# tulip_breakout.net
KiCad netlist of a schematic drawn in EAGLE
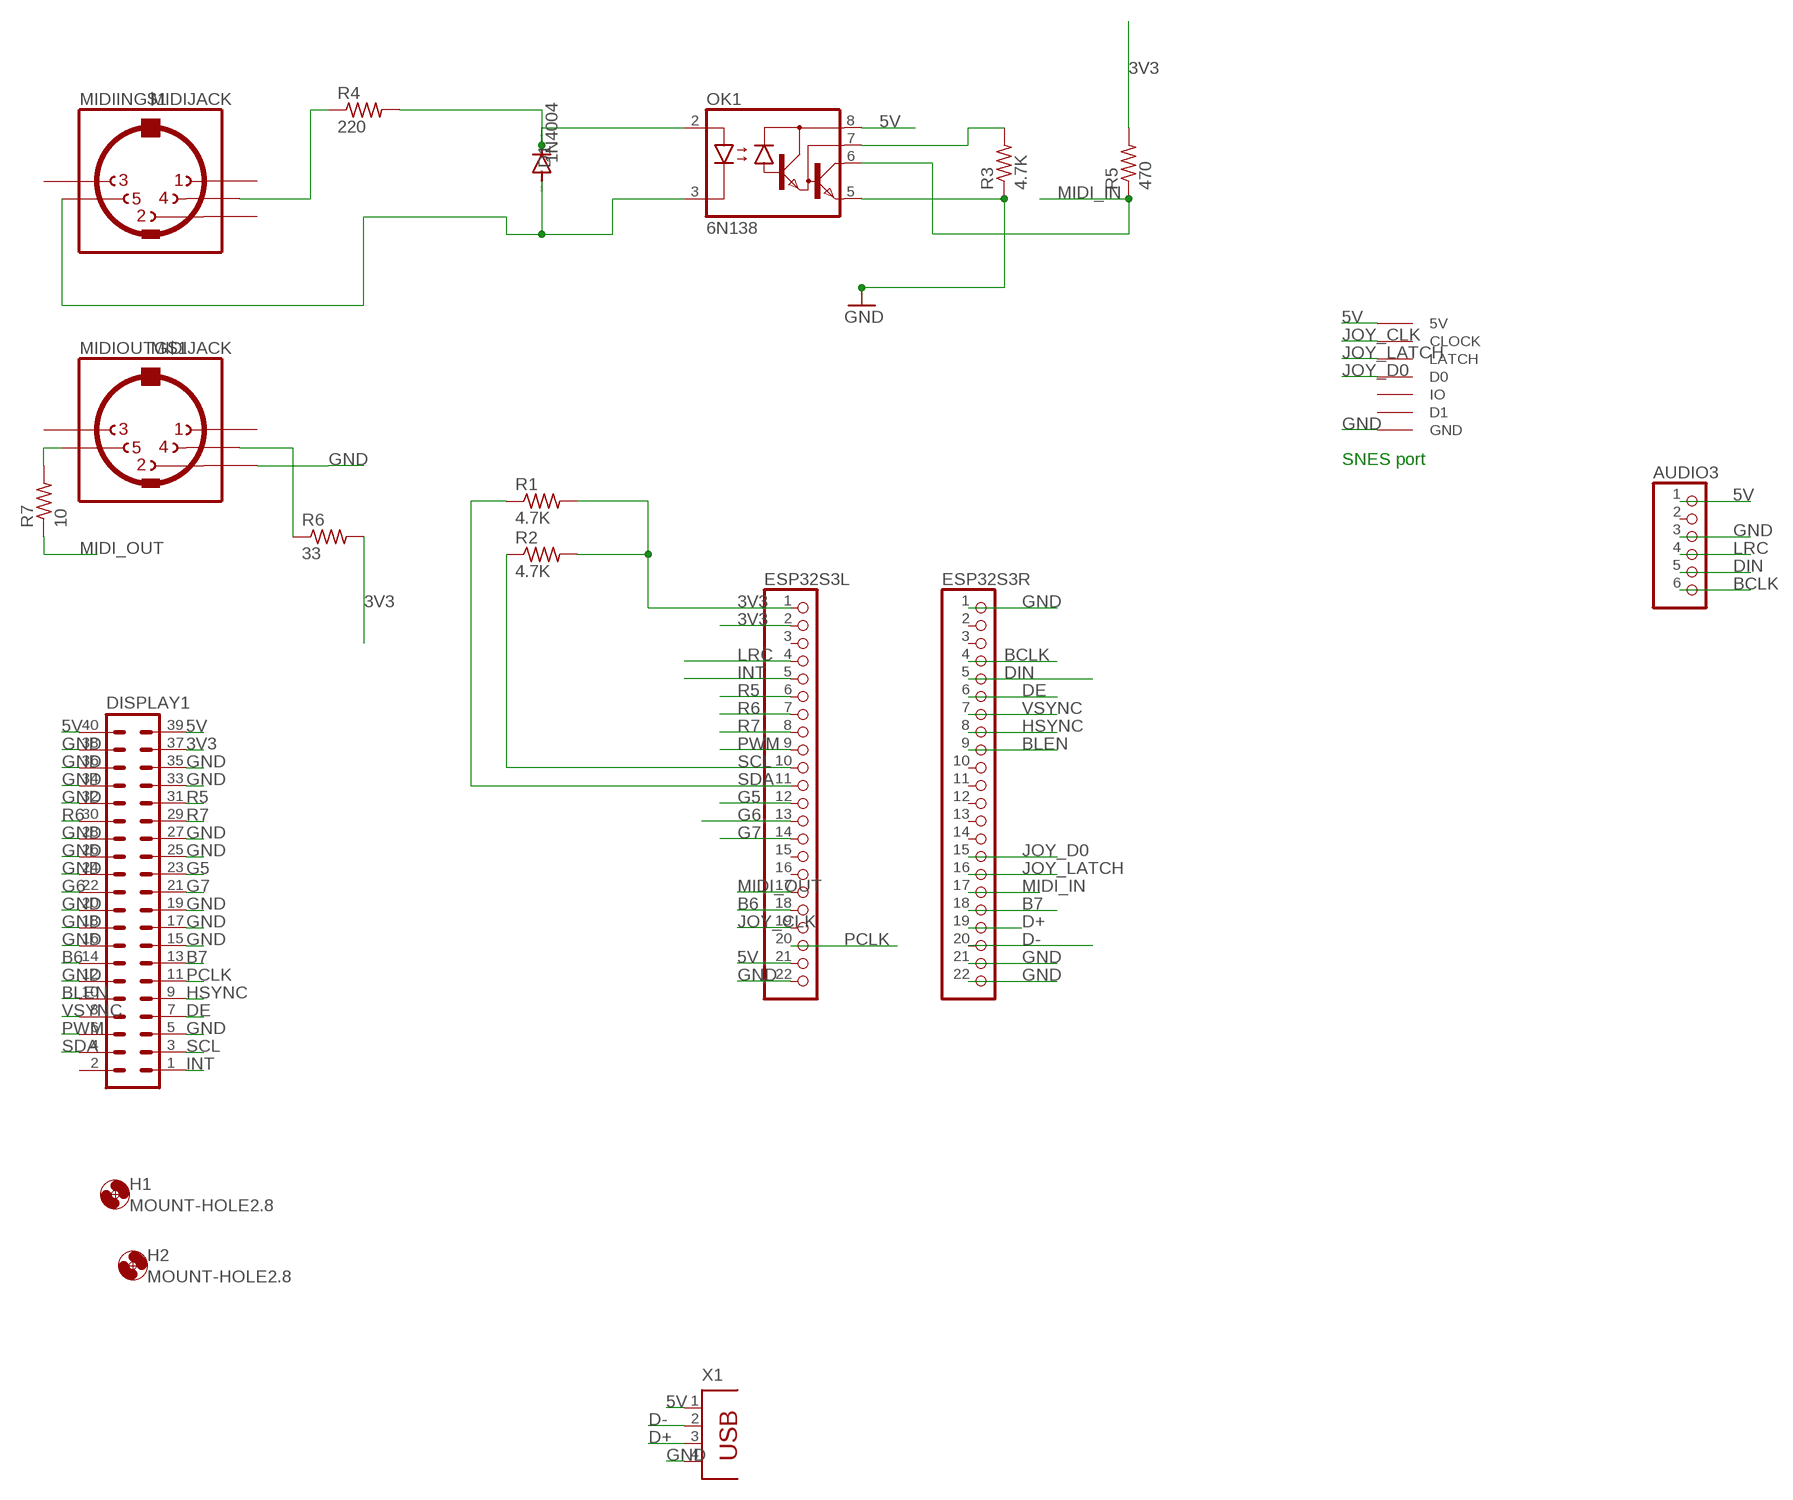
[diagram p0: schematic, sheet 1]

(export (version "E")
  (design (tool "Eeschema 10.0.6"))
  (components
    (comp (ref "AUDIO3")
      (value "PINHD-1X6")
      (footprint "eagle-import:1X06")
      (libsource (lib "eagle-import") (part "PINHD-1X6"))
    )
    (comp (ref "D1")
      (value "1N4004")
      (footprint "eagle-import:DO41-10")
      (libsource (lib "eagle-import") (part "1N4004"))
    )
    (comp (ref "DISPLAY1")
      (value "MA20-2")
      (footprint "eagle-import:MA20-2")
      (libsource (lib "eagle-import") (part "MA20-2"))
    )
    (comp (ref "ESP32S3L")
      (value "PINHD-1X22")
      (footprint "eagle-import:1X22")
      (libsource (lib "eagle-import") (part "PINHD-1X22"))
    )
    (comp (ref "ESP32S3R")
      (value "PINHD-1X22")
      (footprint "eagle-import:1X22")
      (libsource (lib "eagle-import") (part "PINHD-1X22"))
    )
    (comp (ref "H1")
      (value "MOUNT-HOLE2.8")
      (footprint "eagle-import:2,8")
      (libsource (lib "eagle-import") (part "MOUNT-HOLE2.8"))
    )
    (comp (ref "H2")
      (value "MOUNT-HOLE2.8")
      (footprint "eagle-import:2,8")
      (libsource (lib "eagle-import") (part "MOUNT-HOLE2.8"))
    )
    (comp (ref "MIDIIN")
      (value "MIDIJACK")
      (footprint "eagle-import:CP-2350")
      (libsource (lib "eagle-import") (part "MIDIJACK"))
    )
    (comp (ref "MIDIOUT")
      (value "MIDIJACK")
      (footprint "eagle-import:CP-2350")
      (libsource (lib "eagle-import") (part "MIDIJACK"))
    )
    (comp (ref "OK1")
      (value "6N138")
      (footprint "eagle-import:DIL08")
      (fields (field (name "MF") "VISHAY/TELEFUNKEN"))
      (libsource (lib "eagle-import") (part "6N138"))
    )
    (comp (ref "R1")
      (value "4.7K")
      (footprint "eagle-import:0207_12")
      (libsource (lib "eagle-import") (part "R-US_0207/12"))
    )
    (comp (ref "R2")
      (value "4.7K")
      (footprint "eagle-import:0207_12")
      (libsource (lib "eagle-import") (part "R-US_0207/12"))
    )
    (comp (ref "R3")
      (value "4.7K")
      (footprint "eagle-import:0207_12")
      (libsource (lib "eagle-import") (part "R-US_0207/12"))
    )
    (comp (ref "R4")
      (value "220")
      (footprint "eagle-import:0207_12")
      (libsource (lib "eagle-import") (part "R-US_0207/12"))
    )
    (comp (ref "R5")
      (value "470")
      (footprint "eagle-import:0207_12")
      (libsource (lib "eagle-import") (part "R-US_0207/12"))
    )
    (comp (ref "R6")
      (value "33")
      (footprint "eagle-import:0207_12")
      (libsource (lib "eagle-import") (part "R-US_0207/12"))
    )
    (comp (ref "R7")
      (value "10")
      (footprint "eagle-import:0207_12")
      (libsource (lib "eagle-import") (part "R-US_0207/12"))
    )
    (comp (ref "U$2")
      (value "SNESCONN")
      (footprint "eagle-import:SNESCONN")
      (libsource (lib "eagle-import") (part "SNESCONN"))
    )
    (comp (ref "X1")
      (value "PN87520")
      (footprint "eagle-import:PN87520")
      (libsource (lib "eagle-import") (part "PN87520"))
    )
  )
  (nets
    (net (code "1") (name "/3V3") (class "Default")
      (node (ref "DISPLAY1") (pin "37") (pinfunction "37_37") (pintype "passive"))
      (node (ref "ESP32S3L") (pin "1") (pinfunction "1_1") (pintype "passive"))
      (node (ref "ESP32S3L") (pin "2") (pinfunction "2_2") (pintype "passive"))
      (node (ref "R1") (pin "2") (pinfunction "2_2") (pintype "passive"))
      (node (ref "R2") (pin "2") (pinfunction "2_2") (pintype "passive"))
      (node (ref "R5") (pin "2") (pinfunction "2_2") (pintype "passive"))
      (node (ref "R6") (pin "2") (pinfunction "2_2") (pintype "passive"))
    )
    (net (code "2") (name "/5V") (class "Default")
      (node (ref "AUDIO3") (pin "1") (pinfunction "1_1") (pintype "passive"))
      (node (ref "DISPLAY1") (pin "39") (pinfunction "39_39") (pintype "passive"))
      (node (ref "DISPLAY1") (pin "40") (pinfunction "40_40") (pintype "passive"))
      (node (ref "ESP32S3L") (pin "21") (pinfunction "21_21") (pintype "passive"))
      (node (ref "OK1") (pin "8") (pinfunction "VCC_8") (pintype "passive"))
      (node (ref "U$2") (pin "5V") (pinfunction "5V_5V") (pintype "input"))
      (node (ref "X1") (pin "1") (pinfunction "1_1") (pintype "passive"))
    )
    (net (code "3") (name "/B6") (class "Default")
      (node (ref "DISPLAY1") (pin "14") (pinfunction "14_14") (pintype "passive"))
      (node (ref "ESP32S3L") (pin "18") (pinfunction "18_18") (pintype "passive"))
    )
    (net (code "4") (name "/B7") (class "Default")
      (node (ref "DISPLAY1") (pin "13") (pinfunction "13_13") (pintype "passive"))
      (node (ref "ESP32S3R") (pin "18") (pinfunction "18_18") (pintype "passive"))
    )
    (net (code "5") (name "/BCLK") (class "Default")
      (node (ref "AUDIO3") (pin "6") (pinfunction "6_6") (pintype "passive"))
      (node (ref "ESP32S3R") (pin "4") (pinfunction "4_4") (pintype "passive"))
    )
    (net (code "6") (name "/BLEN") (class "Default")
      (node (ref "DISPLAY1") (pin "10") (pinfunction "10_10") (pintype "passive"))
      (node (ref "ESP32S3R") (pin "9") (pinfunction "9_9") (pintype "passive"))
    )
    (net (code "7") (name "/D+") (class "Default")
      (node (ref "ESP32S3R") (pin "19") (pinfunction "19_19") (pintype "passive"))
      (node (ref "X1") (pin "3") (pinfunction "3_3") (pintype "passive"))
    )
    (net (code "8") (name "/D-") (class "Default")
      (node (ref "ESP32S3R") (pin "20") (pinfunction "20_20") (pintype "passive"))
      (node (ref "X1") (pin "2") (pinfunction "2_2") (pintype "passive"))
    )
    (net (code "9") (name "/DE") (class "Default")
      (node (ref "DISPLAY1") (pin "7") (pinfunction "7_7") (pintype "passive"))
      (node (ref "ESP32S3R") (pin "6") (pinfunction "6_6") (pintype "passive"))
    )
    (net (code "10") (name "/DIN") (class "Default")
      (node (ref "AUDIO3") (pin "5") (pinfunction "5_5") (pintype "passive"))
      (node (ref "ESP32S3R") (pin "5") (pinfunction "5_5") (pintype "passive"))
    )
    (net (code "11") (name "/G5") (class "Default")
      (node (ref "DISPLAY1") (pin "23") (pinfunction "23_23") (pintype "passive"))
      (node (ref "ESP32S3L") (pin "12") (pinfunction "12_12") (pintype "passive"))
    )
    (net (code "12") (name "/G6") (class "Default")
      (node (ref "DISPLAY1") (pin "22") (pinfunction "22_22") (pintype "passive"))
      (node (ref "ESP32S3L") (pin "13") (pinfunction "13_13") (pintype "passive"))
    )
    (net (code "13") (name "/G7") (class "Default")
      (node (ref "DISPLAY1") (pin "21") (pinfunction "21_21") (pintype "passive"))
      (node (ref "ESP32S3L") (pin "14") (pinfunction "14_14") (pintype "passive"))
    )
    (net (code "14") (name "/HSYNC") (class "Default")
      (node (ref "DISPLAY1") (pin "9") (pinfunction "9_9") (pintype "passive"))
      (node (ref "ESP32S3R") (pin "8") (pinfunction "8_8") (pintype "passive"))
    )
    (net (code "15") (name "/INT") (class "Default")
      (node (ref "DISPLAY1") (pin "1") (pinfunction "1_1") (pintype "passive"))
      (node (ref "ESP32S3L") (pin "5") (pinfunction "5_5") (pintype "passive"))
    )
    (net (code "16") (name "/JOY_CLK") (class "Default")
      (node (ref "ESP32S3L") (pin "19") (pinfunction "19_19") (pintype "passive"))
      (node (ref "U$2") (pin "CLOCK") (pinfunction "CLOCK_CLOCK") (pintype "input"))
    )
    (net (code "17") (name "/JOY_D0") (class "Default")
      (node (ref "ESP32S3R") (pin "15") (pinfunction "15_15") (pintype "passive"))
      (node (ref "U$2") (pin "D0") (pinfunction "D0_D0") (pintype "bidirectional"))
    )
    (net (code "18") (name "/JOY_LATCH") (class "Default")
      (node (ref "ESP32S3R") (pin "16") (pinfunction "16_16") (pintype "passive"))
      (node (ref "U$2") (pin "LATCH") (pinfunction "LATCH_LATCH") (pintype "input"))
    )
    (net (code "19") (name "/LRC") (class "Default")
      (node (ref "AUDIO3") (pin "4") (pinfunction "4_4") (pintype "passive"))
      (node (ref "ESP32S3L") (pin "4") (pinfunction "4_4") (pintype "passive"))
    )
    (net (code "20") (name "/MIDI_IN") (class "Default")
      (node (ref "ESP32S3R") (pin "17") (pinfunction "17_17") (pintype "passive"))
      (node (ref "OK1") (pin "6") (pinfunction "VO_6") (pintype "passive"))
      (node (ref "R5") (pin "1") (pinfunction "1_1") (pintype "passive"))
    )
    (net (code "21") (name "/MIDI_OUT") (class "Default")
      (node (ref "ESP32S3L") (pin "17") (pinfunction "17_17") (pintype "passive"))
      (node (ref "R7") (pin "1") (pinfunction "1_1") (pintype "passive"))
    )
    (net (code "22") (name "/PCLK") (class "Default")
      (node (ref "DISPLAY1") (pin "11") (pinfunction "11_11") (pintype "passive"))
      (node (ref "ESP32S3L") (pin "20") (pinfunction "20_20") (pintype "passive"))
    )
    (net (code "23") (name "/PWM") (class "Default")
      (node (ref "DISPLAY1") (pin "6") (pinfunction "6_6") (pintype "passive"))
      (node (ref "ESP32S3L") (pin "9") (pinfunction "9_9") (pintype "passive"))
    )
    (net (code "24") (name "/R5") (class "Default")
      (node (ref "DISPLAY1") (pin "31") (pinfunction "31_31") (pintype "passive"))
      (node (ref "ESP32S3L") (pin "6") (pinfunction "6_6") (pintype "passive"))
    )
    (net (code "25") (name "/R6") (class "Default")
      (node (ref "DISPLAY1") (pin "30") (pinfunction "30_30") (pintype "passive"))
      (node (ref "ESP32S3L") (pin "7") (pinfunction "7_7") (pintype "passive"))
    )
    (net (code "26") (name "/R7") (class "Default")
      (node (ref "DISPLAY1") (pin "29") (pinfunction "29_29") (pintype "passive"))
      (node (ref "ESP32S3L") (pin "8") (pinfunction "8_8") (pintype "passive"))
    )
    (net (code "27") (name "/SCL") (class "Default")
      (node (ref "DISPLAY1") (pin "3") (pinfunction "3_3") (pintype "passive"))
      (node (ref "ESP32S3L") (pin "10") (pinfunction "10_10") (pintype "passive"))
      (node (ref "R2") (pin "1") (pinfunction "1_1") (pintype "passive"))
    )
    (net (code "28") (name "/SDA") (class "Default")
      (node (ref "DISPLAY1") (pin "4") (pinfunction "4_4") (pintype "passive"))
      (node (ref "ESP32S3L") (pin "11") (pinfunction "11_11") (pintype "passive"))
      (node (ref "R1") (pin "1") (pinfunction "1_1") (pintype "passive"))
    )
    (net (code "29") (name "/VSYNC") (class "Default")
      (node (ref "DISPLAY1") (pin "8") (pinfunction "8_8") (pintype "passive"))
      (node (ref "ESP32S3R") (pin "7") (pinfunction "7_7") (pintype "passive"))
    )
    (net (code "30") (name "GND") (class "Default")
      (node (ref "AUDIO3") (pin "3") (pinfunction "3_3") (pintype "passive"))
      (node (ref "DISPLAY1") (pin "12") (pinfunction "12_12") (pintype "passive"))
      (node (ref "DISPLAY1") (pin "15") (pinfunction "15_15") (pintype "passive"))
      (node (ref "DISPLAY1") (pin "16") (pinfunction "16_16") (pintype "passive"))
      (node (ref "DISPLAY1") (pin "17") (pinfunction "17_17") (pintype "passive"))
      (node (ref "DISPLAY1") (pin "18") (pinfunction "18_18") (pintype "passive"))
      (node (ref "DISPLAY1") (pin "19") (pinfunction "19_19") (pintype "passive"))
      (node (ref "DISPLAY1") (pin "20") (pinfunction "20_20") (pintype "passive"))
      (node (ref "DISPLAY1") (pin "24") (pinfunction "24_24") (pintype "passive"))
      (node (ref "DISPLAY1") (pin "25") (pinfunction "25_25") (pintype "passive"))
      (node (ref "DISPLAY1") (pin "26") (pinfunction "26_26") (pintype "passive"))
      (node (ref "DISPLAY1") (pin "27") (pinfunction "27_27") (pintype "passive"))
      (node (ref "DISPLAY1") (pin "28") (pinfunction "28_28") (pintype "passive"))
      (node (ref "DISPLAY1") (pin "32") (pinfunction "32_32") (pintype "passive"))
      (node (ref "DISPLAY1") (pin "33") (pinfunction "33_33") (pintype "passive"))
      (node (ref "DISPLAY1") (pin "34") (pinfunction "34_34") (pintype "passive"))
      (node (ref "DISPLAY1") (pin "35") (pinfunction "35_35") (pintype "passive"))
      (node (ref "DISPLAY1") (pin "36") (pinfunction "36_36") (pintype "passive"))
      (node (ref "DISPLAY1") (pin "38") (pinfunction "38_38") (pintype "passive"))
      (node (ref "DISPLAY1") (pin "5") (pinfunction "5_5") (pintype "passive"))
      (node (ref "ESP32S3L") (pin "22") (pinfunction "22_22") (pintype "passive"))
      (node (ref "ESP32S3R") (pin "1") (pinfunction "1_1") (pintype "passive"))
      (node (ref "ESP32S3R") (pin "21") (pinfunction "21_21") (pintype "passive"))
      (node (ref "ESP32S3R") (pin "22") (pinfunction "22_22") (pintype "passive"))
      (node (ref "MIDIOUT") (pin "2") (pinfunction "2_2") (pintype "passive"))
      (node (ref "OK1") (pin "5") (pinfunction "GND_5") (pintype "passive"))
      (node (ref "R3") (pin "1") (pinfunction "1_1") (pintype "passive"))
      (node (ref "U$2") (pin "GND") (pinfunction "GND_GND") (pintype "power_in"))
      (node (ref "X1") (pin "4") (pinfunction "4_4") (pintype "passive"))
    )
    (net (code "31") (name "Net-(MIDIIN-Pad4)") (class "Default")
      (node (ref "MIDIIN") (pin "4") (pinfunction "4_4") (pintype "passive"))
      (node (ref "R4") (pin "1") (pinfunction "1_1") (pintype "passive"))
    )
    (net (code "32") (name "Net-(MIDIOUT-Pad4)") (class "Default")
      (node (ref "MIDIOUT") (pin "4") (pinfunction "4_4") (pintype "passive"))
      (node (ref "R6") (pin "1") (pinfunction "1_1") (pintype "passive"))
    )
    (net (code "33") (name "Net-(MIDIOUT-Pad5)") (class "Default")
      (node (ref "MIDIOUT") (pin "5") (pinfunction "5_5") (pintype "passive"))
      (node (ref "R7") (pin "2") (pinfunction "2_2") (pintype "passive"))
    )
    (net (code "34") (name "Net-(OK1-A)") (class "Default")
      (node (ref "D1") (pin "C") (pinfunction "C_C") (pintype "passive"))
      (node (ref "OK1") (pin "2") (pinfunction "A_2") (pintype "passive"))
      (node (ref "R4") (pin "2") (pinfunction "2_2") (pintype "passive"))
    )
    (net (code "35") (name "Net-(OK1-C)") (class "Default")
      (node (ref "D1") (pin "A") (pinfunction "A_A") (pintype "passive"))
      (node (ref "MIDIIN") (pin "5") (pinfunction "5_5") (pintype "passive"))
      (node (ref "OK1") (pin "3") (pinfunction "C_3") (pintype "passive"))
    )
    (net (code "36") (name "Net-(OK1-VB)") (class "Default")
      (node (ref "OK1") (pin "7") (pinfunction "VB_7") (pintype "passive"))
      (node (ref "R3") (pin "2") (pinfunction "2_2") (pintype "passive"))
    )
    (net (code "37") (name "unconnected-(AUDIO3-Pad2)") (class "Default")
      (node (ref "AUDIO3") (pin "2") (pinfunction "2_2") (pintype "passive"))
    )
    (net (code "38") (name "unconnected-(DISPLAY1-Pad2)") (class "Default")
      (node (ref "DISPLAY1") (pin "2") (pinfunction "2_2") (pintype "passive"))
    )
    (net (code "39") (name "unconnected-(ESP32S3L-Pad3)") (class "Default")
      (node (ref "ESP32S3L") (pin "3") (pinfunction "3_3") (pintype "passive"))
    )
    (net (code "40") (name "unconnected-(ESP32S3L-Pad15)") (class "Default")
      (node (ref "ESP32S3L") (pin "15") (pinfunction "15_15") (pintype "passive"))
    )
    (net (code "41") (name "unconnected-(ESP32S3L-Pad16)") (class "Default")
      (node (ref "ESP32S3L") (pin "16") (pinfunction "16_16") (pintype "passive"))
    )
    (net (code "42") (name "unconnected-(ESP32S3R-Pad2)") (class "Default")
      (node (ref "ESP32S3R") (pin "2") (pinfunction "2_2") (pintype "passive"))
    )
    (net (code "43") (name "unconnected-(ESP32S3R-Pad3)") (class "Default")
      (node (ref "ESP32S3R") (pin "3") (pinfunction "3_3") (pintype "passive"))
    )
    (net (code "44") (name "unconnected-(ESP32S3R-Pad10)") (class "Default")
      (node (ref "ESP32S3R") (pin "10") (pinfunction "10_10") (pintype "passive"))
    )
    (net (code "45") (name "unconnected-(ESP32S3R-Pad11)") (class "Default")
      (node (ref "ESP32S3R") (pin "11") (pinfunction "11_11") (pintype "passive"))
    )
    (net (code "46") (name "unconnected-(ESP32S3R-Pad12)") (class "Default")
      (node (ref "ESP32S3R") (pin "12") (pinfunction "12_12") (pintype "passive"))
    )
    (net (code "47") (name "unconnected-(ESP32S3R-Pad13)") (class "Default")
      (node (ref "ESP32S3R") (pin "13") (pinfunction "13_13") (pintype "passive"))
    )
    (net (code "48") (name "unconnected-(ESP32S3R-Pad14)") (class "Default")
      (node (ref "ESP32S3R") (pin "14") (pinfunction "14_14") (pintype "passive"))
    )
    (net (code "49") (name "unconnected-(MIDIIN-Pad1)") (class "Default")
      (node (ref "MIDIIN") (pin "1") (pinfunction "1_1") (pintype "passive"))
    )
    (net (code "50") (name "unconnected-(MIDIIN-Pad2)") (class "Default")
      (node (ref "MIDIIN") (pin "2") (pinfunction "2_2") (pintype "passive"))
    )
    (net (code "51") (name "unconnected-(MIDIIN-Pad3)") (class "Default")
      (node (ref "MIDIIN") (pin "3") (pinfunction "3_3") (pintype "passive"))
    )
    (net (code "52") (name "unconnected-(MIDIOUT-Pad1)") (class "Default")
      (node (ref "MIDIOUT") (pin "1") (pinfunction "1_1") (pintype "passive"))
    )
    (net (code "53") (name "unconnected-(MIDIOUT-Pad3)") (class "Default")
      (node (ref "MIDIOUT") (pin "3") (pinfunction "3_3") (pintype "passive"))
    )
    (net (code "54") (name "unconnected-(U$2-PadD1)") (class "Default")
      (node (ref "U$2") (pin "D1") (pinfunction "D1_D1") (pintype "bidirectional"))
    )
    (net (code "55") (name "unconnected-(U$2-PadIO)") (class "Default")
      (node (ref "U$2") (pin "IO") (pinfunction "IO_IO") (pintype "bidirectional"))
    )
  )
)
